# bln-000.net
KiCad netlist of a schematic drawn in EAGLE
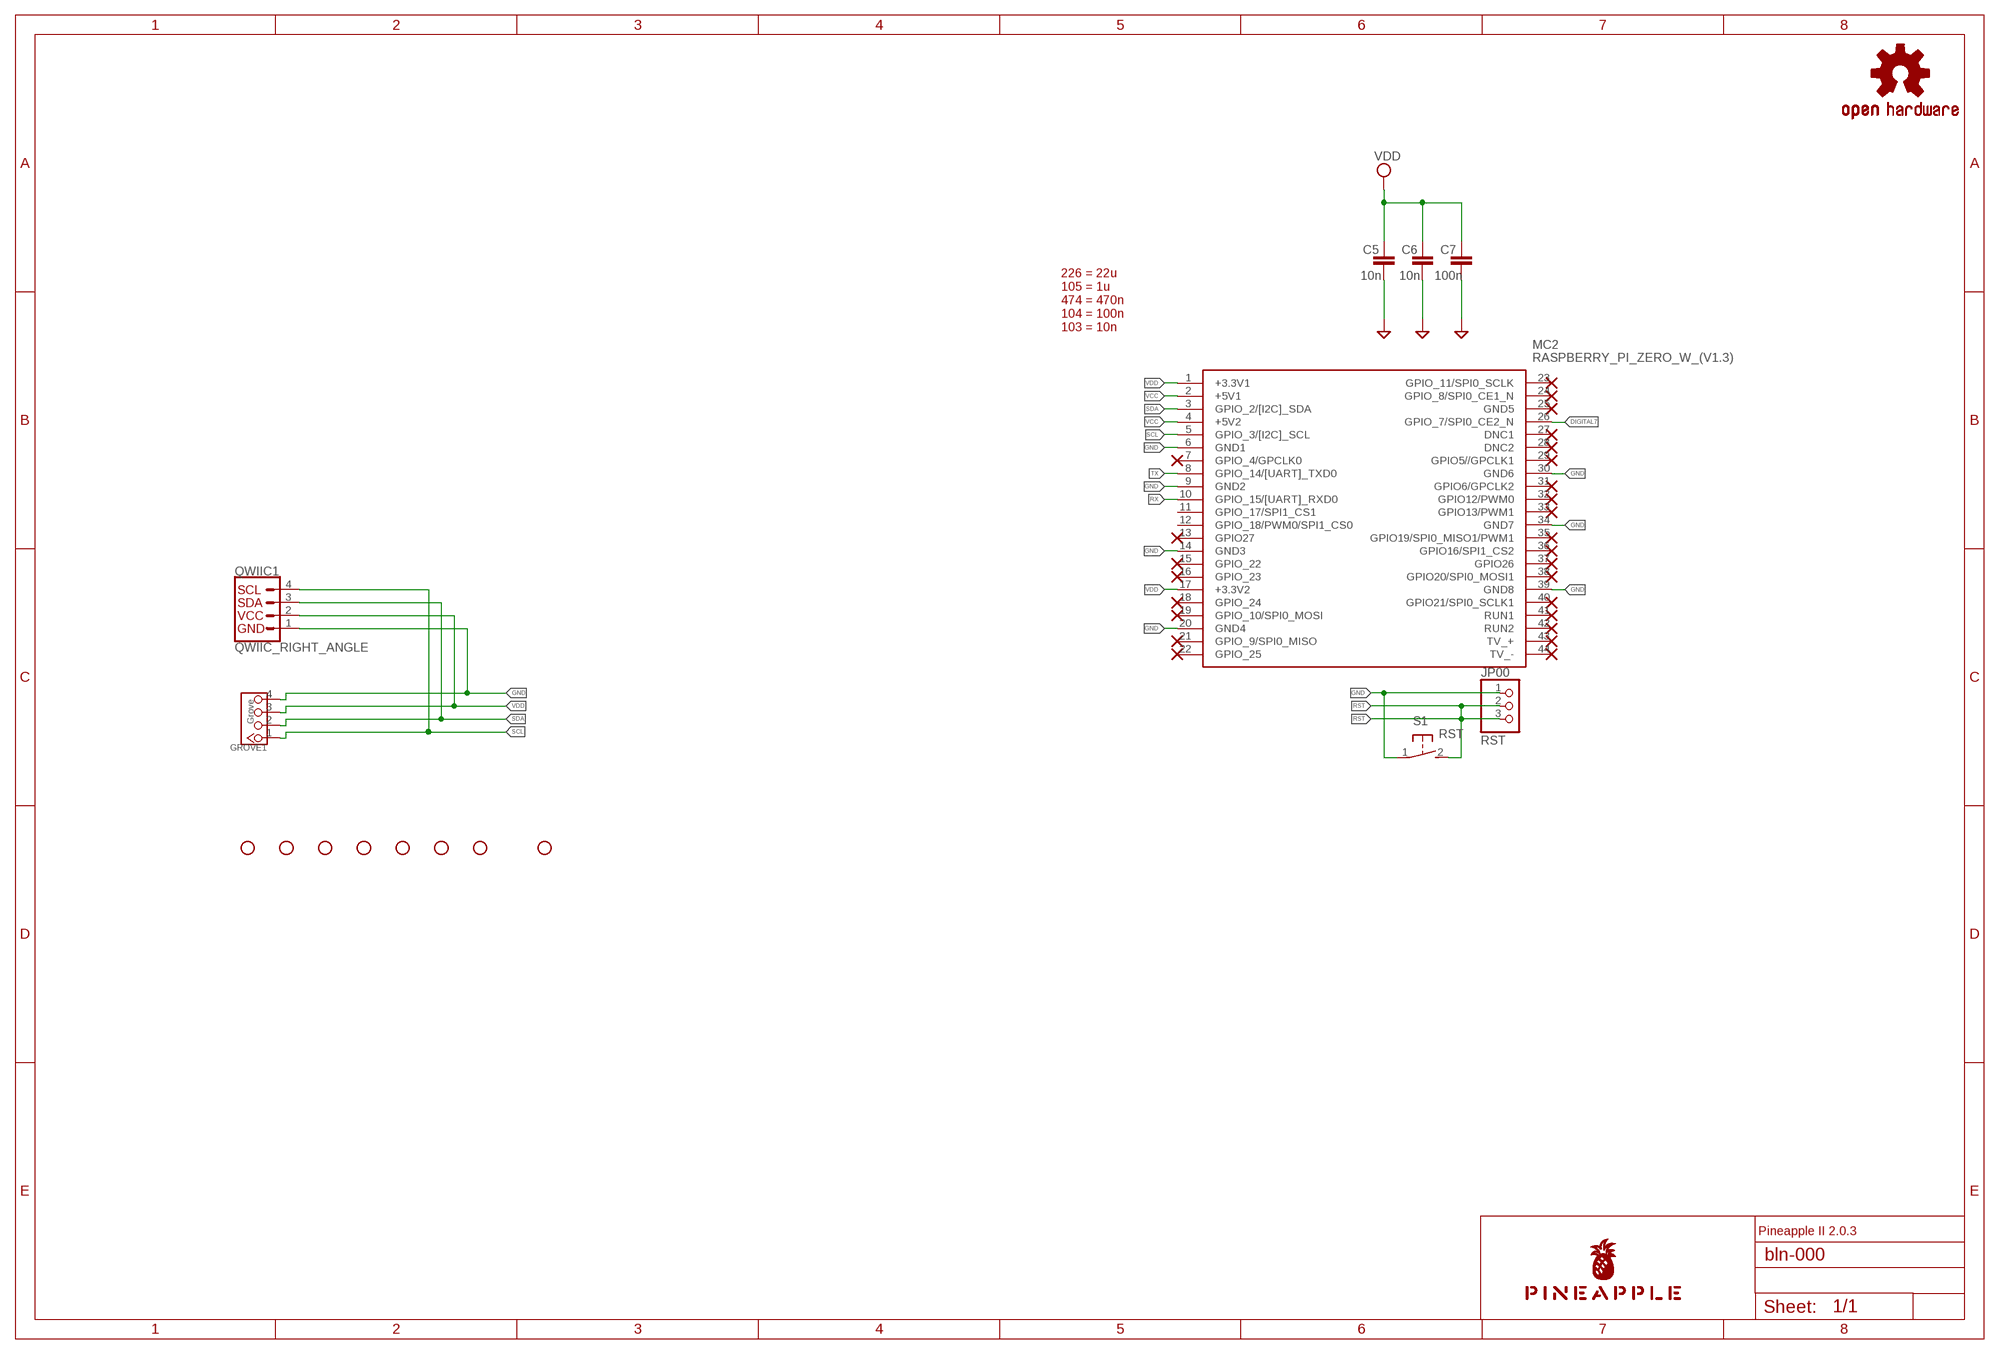
[diagram p0: schematic, sheet 1]

(export (version "E")
  (design (tool "Eeschema 10.0.6"))
  (components
    (comp (ref "C5")
      (value "10n")
      (footprint "eagle-import:C025-024X044")
      (libsource (lib "eagle-import") (part "C-EU025-024X044"))
    )
    (comp (ref "C6")
      (value "10n")
      (footprint "eagle-import:C025-024X044")
      (libsource (lib "eagle-import") (part "C-EU025-024X044"))
    )
    (comp (ref "C7")
      (value "100n")
      (footprint "eagle-import:C025-024X044")
      (libsource (lib "eagle-import") (part "C-EU025-024X044"))
    )
    (comp (ref "GROVE1")
      (value "Grove")
      (footprint "eagle-import:4P-2.0-90D")
      (libsource (lib "eagle-import") (part "TWIG-4P-2.0'90D'"))
    )
    (comp (ref "H1")
      (value "STAND-OFF")
      (footprint "eagle-import:STAND-OFF")
      (libsource (lib "eagle-import") (part "STAND-OFF"))
    )
    (comp (ref "H2")
      (value "STAND-OFF")
      (footprint "eagle-import:STAND-OFF")
      (libsource (lib "eagle-import") (part "STAND-OFF"))
    )
    (comp (ref "H3")
      (value "STAND-OFF")
      (footprint "eagle-import:STAND-OFF")
      (libsource (lib "eagle-import") (part "STAND-OFF"))
    )
    (comp (ref "H4")
      (value "STAND-OFF")
      (footprint "eagle-import:STAND-OFF")
      (libsource (lib "eagle-import") (part "STAND-OFF"))
    )
    (comp (ref "H5")
      (value "STAND-OFF")
      (footprint "eagle-import:STAND-OFF")
      (libsource (lib "eagle-import") (part "STAND-OFF"))
    )
    (comp (ref "H6")
      (value "STAND-OFF")
      (footprint "eagle-import:STAND-OFF")
      (libsource (lib "eagle-import") (part "STAND-OFF"))
    )
    (comp (ref "H7")
      (value "STAND-OFF")
      (footprint "eagle-import:STAND-OFF")
      (libsource (lib "eagle-import") (part "STAND-OFF"))
    )
    (comp (ref "H8")
      (value "STAND-OFF")
      (footprint "eagle-import:STAND-OFF")
      (libsource (lib "eagle-import") (part "STAND-OFF"))
    )
    (comp (ref "JP00")
      (value "RST")
      (footprint "eagle-import:1X03")
      (libsource (lib "eagle-import") (part "PINHD-1X3"))
    )
    (comp (ref "LOGO1")
      (value "OSHW-LOGOS-COPPER")
      (footprint "eagle-import:OSHW-LOGO-S_COPPER")
      (libsource (lib "eagle-import") (part "OSHW-LOGOS-COPPER"))
    )
    (comp (ref "MC2")
      (value "RASPBERRY_PI_ZERO_W_(V1.3)")
      (footprint "eagle-import:RASPBERRYPIZEROWV13")
      (fields (field (name "ARROW_PART_NUMBER") "Raspberry Pi Zero W (v1.3)"))
      (libsource (lib "eagle-import") (part "RASPBERRY_PI_ZERO_W_(V1.3)"))
    )
    (comp (ref "QWIIC1")
      (value "QWIIC_RIGHT_ANGLE")
      (footprint "eagle-import:JST04_1MM_RA")
      (libsource (lib "eagle-import") (part "QWIIC_CONNECTORJS-1MM"))
    )
    (comp (ref "S1")
      (value "RST")
      (footprint "eagle-import:B3F-31XX")
      (fields (field (name "MPN") "B3F-3100"))
      (libsource (lib "eagle-import") (part "31-XX"))
    )
    (comp (ref "U$1")
      (value "PINEAPPLE450_SILK")
      (footprint "eagle-import:PINEAPPLE450_SILK")
      (libsource (lib "eagle-import") (part "PINEAPPLE450_SILK"))
    )
  )
  (nets
    (net (code "1") (name "DIGITAL7") (class "Default")
      (node (ref "MC2") (pin "26") (pinfunction "GPIO_7/SPI0_CE2_N_26") (pintype "bidirectional"))
    )
    (net (code "2") (name "GND") (class "Default")
      (node (ref "C5") (pin "2") (pinfunction "2_2") (pintype "passive"))
      (node (ref "C6") (pin "2") (pinfunction "2_2") (pintype "passive"))
      (node (ref "C7") (pin "2") (pinfunction "2_2") (pintype "passive"))
      (node (ref "GROVE1") (pin "4") (pinfunction "4_4") (pintype "bidirectional"))
      (node (ref "JP00") (pin "1") (pinfunction "1_1") (pintype "passive"))
      (node (ref "MC2") (pin "14") (pinfunction "GND3_14") (pintype "bidirectional"))
      (node (ref "MC2") (pin "20") (pinfunction "GND4_20") (pintype "bidirectional"))
      (node (ref "MC2") (pin "30") (pinfunction "GND6_30") (pintype "bidirectional"))
      (node (ref "MC2") (pin "34") (pinfunction "GND7_34") (pintype "bidirectional"))
      (node (ref "MC2") (pin "39") (pinfunction "GND8_39") (pintype "bidirectional"))
      (node (ref "MC2") (pin "6") (pinfunction "GND1_6") (pintype "bidirectional"))
      (node (ref "MC2") (pin "9") (pinfunction "GND2_9") (pintype "bidirectional"))
      (node (ref "QWIIC1") (pin "1") (pinfunction "1_1") (pintype "power_in"))
      (node (ref "S1") (pin "1") (pinfunction "P_1") (pintype "passive"))
    )
    (net (code "3") (name "RST") (class "Default")
      (node (ref "JP00") (pin "2") (pinfunction "2_2") (pintype "passive"))
      (node (ref "JP00") (pin "3") (pinfunction "3_3") (pintype "passive"))
      (node (ref "S1") (pin "2") (pinfunction "S_2") (pintype "passive"))
    )
    (net (code "4") (name "RX") (class "Default")
      (node (ref "MC2") (pin "10") (pinfunction "GPIO_15/[UART]_RXD0_10") (pintype "bidirectional"))
    )
    (net (code "5") (name "SCL") (class "Default")
      (node (ref "GROVE1") (pin "1") (pinfunction "1_1") (pintype "bidirectional"))
      (node (ref "MC2") (pin "5") (pinfunction "GPIO_3/[I2C]_SCL_5") (pintype "bidirectional"))
      (node (ref "QWIIC1") (pin "4") (pinfunction "4_4") (pintype "passive"))
    )
    (net (code "6") (name "SDA") (class "Default")
      (node (ref "GROVE1") (pin "2") (pinfunction "2_2") (pintype "bidirectional"))
      (node (ref "MC2") (pin "3") (pinfunction "GPIO_2/[I2C]_SDA_3") (pintype "bidirectional"))
      (node (ref "QWIIC1") (pin "3") (pinfunction "3_3") (pintype "passive"))
    )
    (net (code "7") (name "TX") (class "Default")
      (node (ref "MC2") (pin "8") (pinfunction "GPIO_14/[UART]_TXD0_8") (pintype "bidirectional"))
    )
    (net (code "8") (name "VCC") (class "Default")
      (node (ref "MC2") (pin "2") (pinfunction "+5V1_2") (pintype "bidirectional"))
      (node (ref "MC2") (pin "4") (pinfunction "+5V2_4") (pintype "bidirectional"))
    )
    (net (code "9") (name "VDD") (class "Default")
      (node (ref "C5") (pin "1") (pinfunction "1_1") (pintype "passive"))
      (node (ref "C6") (pin "1") (pinfunction "1_1") (pintype "passive"))
      (node (ref "C7") (pin "1") (pinfunction "1_1") (pintype "passive"))
      (node (ref "GROVE1") (pin "3") (pinfunction "3_3") (pintype "bidirectional"))
      (node (ref "MC2") (pin "1") (pinfunction "+3.3V1_1") (pintype "bidirectional"))
      (node (ref "MC2") (pin "17") (pinfunction "+3.3V2_17") (pintype "bidirectional"))
      (node (ref "QWIIC1") (pin "2") (pinfunction "2_2") (pintype "power_in"))
    )
    (net (code "10") (name "unconnected-(MC2-DNC1-Pad27)") (class "Default")
      (node (ref "MC2") (pin "27") (pinfunction "DNC1_27") (pintype "bidirectional"))
    )
    (net (code "11") (name "unconnected-(MC2-DNC2-Pad28)") (class "Default")
      (node (ref "MC2") (pin "28") (pinfunction "DNC2_28") (pintype "bidirectional"))
    )
    (net (code "12") (name "unconnected-(MC2-GND5-Pad25)") (class "Default")
      (node (ref "MC2") (pin "25") (pinfunction "GND5_25") (pintype "bidirectional"))
    )
    (net (code "13") (name "unconnected-(MC2-GPIO5{slash}{slash}GPCLK1-Pad29)") (class "Default")
      (node (ref "MC2") (pin "29") (pinfunction "GPIO5//GPCLK1_29") (pintype "bidirectional"))
    )
    (net (code "14") (name "unconnected-(MC2-GPIO6{slash}GPCLK2-Pad31)") (class "Default")
      (node (ref "MC2") (pin "31") (pinfunction "GPIO6/GPCLK2_31") (pintype "bidirectional"))
    )
    (net (code "15") (name "unconnected-(MC2-GPIO12{slash}PWM0-Pad32)") (class "Default")
      (node (ref "MC2") (pin "32") (pinfunction "GPIO12/PWM0_32") (pintype "bidirectional"))
    )
    (net (code "16") (name "unconnected-(MC2-GPIO13{slash}PWM1-Pad33)") (class "Default")
      (node (ref "MC2") (pin "33") (pinfunction "GPIO13/PWM1_33") (pintype "bidirectional"))
    )
    (net (code "17") (name "unconnected-(MC2-GPIO16{slash}SPI1_CS2-Pad36)") (class "Default")
      (node (ref "MC2") (pin "36") (pinfunction "GPIO16/SPI1_CS2_36") (pintype "bidirectional"))
    )
    (net (code "18") (name "unconnected-(MC2-GPIO19{slash}SPI0_MISO1{slash}PWM1-Pad35)") (class "Default")
      (node (ref "MC2") (pin "35") (pinfunction "GPIO19/SPI0_MISO1/PWM1_35") (pintype "bidirectional"))
    )
    (net (code "19") (name "unconnected-(MC2-GPIO20{slash}SPI0_MOSI1-Pad38)") (class "Default")
      (node (ref "MC2") (pin "38") (pinfunction "GPIO20/SPI0_MOSI1_38") (pintype "bidirectional"))
    )
    (net (code "20") (name "unconnected-(MC2-GPIO21{slash}SPI0_SCLK1-Pad40)") (class "Default")
      (node (ref "MC2") (pin "40") (pinfunction "GPIO21/SPI0_SCLK1_40") (pintype "bidirectional"))
    )
    (net (code "21") (name "unconnected-(MC2-GPIO26-Pad37)") (class "Default")
      (node (ref "MC2") (pin "37") (pinfunction "GPIO26_37") (pintype "bidirectional"))
    )
    (net (code "22") (name "unconnected-(MC2-GPIO27-Pad13)") (class "Default")
      (node (ref "MC2") (pin "13") (pinfunction "GPIO27_13") (pintype "bidirectional"))
    )
    (net (code "23") (name "unconnected-(MC2-GPIO_4{slash}GPCLK0-Pad7)") (class "Default")
      (node (ref "MC2") (pin "7") (pinfunction "GPIO_4/GPCLK0_7") (pintype "bidirectional"))
    )
    (net (code "24") (name "unconnected-(MC2-GPIO_8{slash}SPI0_CE1_N-Pad24)") (class "Default")
      (node (ref "MC2") (pin "24") (pinfunction "GPIO_8/SPI0_CE1_N_24") (pintype "bidirectional"))
    )
    (net (code "25") (name "unconnected-(MC2-GPIO_9{slash}SPI0_MISO-Pad21)") (class "Default")
      (node (ref "MC2") (pin "21") (pinfunction "GPIO_9/SPI0_MISO_21") (pintype "bidirectional"))
    )
    (net (code "26") (name "unconnected-(MC2-GPIO_10{slash}SPI0_MOSI-Pad19)") (class "Default")
      (node (ref "MC2") (pin "19") (pinfunction "GPIO_10/SPI0_MOSI_19") (pintype "bidirectional"))
    )
    (net (code "27") (name "unconnected-(MC2-GPIO_11{slash}SPI0_SCLK-Pad23)") (class "Default")
      (node (ref "MC2") (pin "23") (pinfunction "GPIO_11/SPI0_SCLK_23") (pintype "bidirectional"))
    )
    (net (code "28") (name "unconnected-(MC2-GPIO_17{slash}SPI1_CS1-Pad11)") (class "Default")
      (node (ref "MC2") (pin "11") (pinfunction "GPIO_17/SPI1_CS1_11") (pintype "bidirectional"))
    )
    (net (code "29") (name "unconnected-(MC2-GPIO_18{slash}PWM0{slash}SPI1_CS0-Pad12)") (class "Default")
      (node (ref "MC2") (pin "12") (pinfunction "GPIO_18/PWM0/SPI1_CS0_12") (pintype "bidirectional"))
    )
    (net (code "30") (name "unconnected-(MC2-GPIO_22-Pad15)") (class "Default")
      (node (ref "MC2") (pin "15") (pinfunction "GPIO_22_15") (pintype "bidirectional"))
    )
    (net (code "31") (name "unconnected-(MC2-GPIO_23-Pad16)") (class "Default")
      (node (ref "MC2") (pin "16") (pinfunction "GPIO_23_16") (pintype "bidirectional"))
    )
    (net (code "32") (name "unconnected-(MC2-GPIO_24-Pad18)") (class "Default")
      (node (ref "MC2") (pin "18") (pinfunction "GPIO_24_18") (pintype "bidirectional"))
    )
    (net (code "33") (name "unconnected-(MC2-GPIO_25-Pad22)") (class "Default")
      (node (ref "MC2") (pin "22") (pinfunction "GPIO_25_22") (pintype "bidirectional"))
    )
    (net (code "34") (name "unconnected-(MC2-RUN1-Pad41)") (class "Default")
      (node (ref "MC2") (pin "41") (pinfunction "RUN1_41") (pintype "bidirectional"))
    )
    (net (code "35") (name "unconnected-(MC2-RUN2-Pad42)") (class "Default")
      (node (ref "MC2") (pin "42") (pinfunction "RUN2_42") (pintype "bidirectional"))
    )
    (net (code "36") (name "unconnected-(MC2-TV_+-Pad43)") (class "Default")
      (node (ref "MC2") (pin "43") (pinfunction "TV_+_43") (pintype "bidirectional"))
    )
    (net (code "37") (name "unconnected-(MC2-TV_--Pad44)") (class "Default")
      (node (ref "MC2") (pin "44") (pinfunction "TV_-_44") (pintype "bidirectional"))
    )
  )
)
